# CH32V203RBT6-R1.net
KiCad netlist of a schematic drawn in Altium Designer
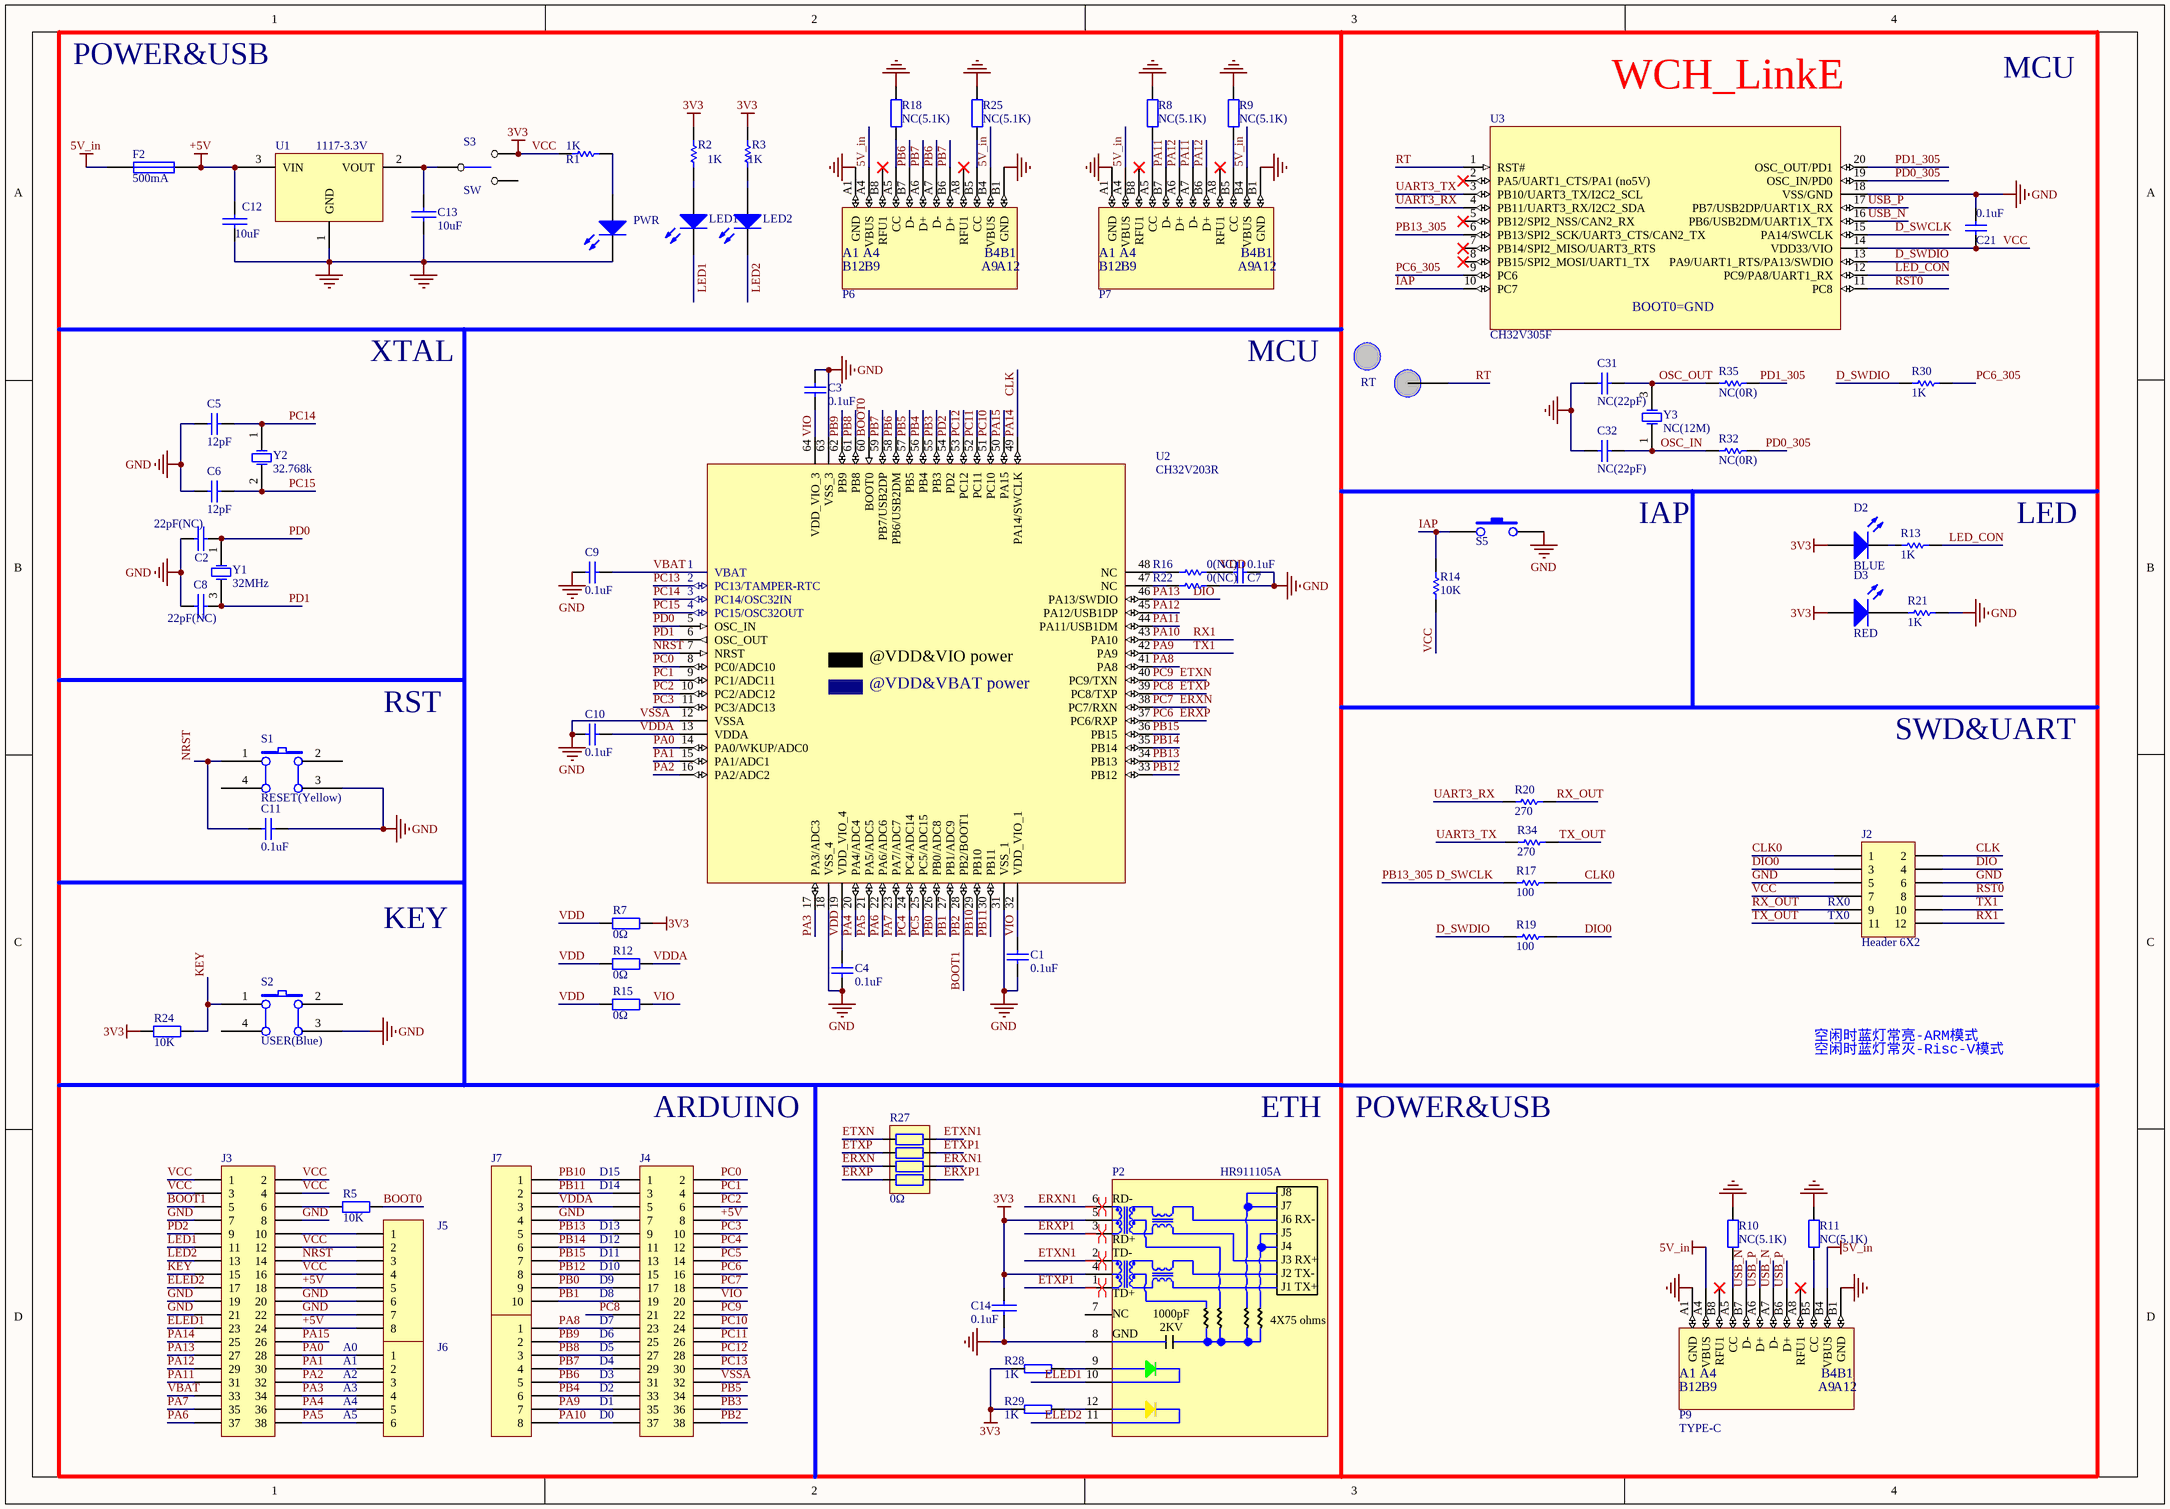
[diagram p0: CH32V203RBT6-R1.SchDoc]

(export (version "E")
  (design (tool "Eeschema 10.0.6"))
  (components
    (comp (ref "C1")
      (value "0.1uF")
      (footprint "0603_C")
      (description "Capacitor")
      (libsource (lib "Miscellaneous Devices") (part "Cap"))
    )
    (comp (ref "C2")
      (value "22pF(NC)")
      (footprint "0603_C")
      (description "Capacitor")
      (libsource (lib "*") (part "CAP"))
    )
    (comp (ref "C3")
      (value "0.1uF")
      (footprint "0603_C")
      (description "Capacitor")
      (libsource (lib "Miscellaneous Devices") (part "Cap"))
    )
    (comp (ref "C4")
      (value "0.1uF")
      (footprint "0603_C")
      (description "Capacitor")
      (libsource (lib "Miscellaneous Devices") (part "Cap"))
    )
    (comp (ref "C5")
      (value "12pF")
      (footprint "0603_C")
      (description "Capacitor")
      (libsource (lib "Miscellaneous Devices") (part "Cap"))
    )
    (comp (ref "C6")
      (value "12pF")
      (footprint "0603_C")
      (description "Capacitor")
      (libsource (lib "Miscellaneous Devices") (part "Cap"))
    )
    (comp (ref "C7")
      (value "0.1uF")
      (footprint "0603_C")
      (description "Capacitor")
      (libsource (lib "Miscellaneous Devices") (part "Cap"))
    )
    (comp (ref "C8")
      (value "22pF(NC)")
      (footprint "0603_C")
      (description "Capacitor")
      (libsource (lib "*") (part "CAP"))
    )
    (comp (ref "C9")
      (value "0.1uF")
      (footprint "0603_C")
      (description "Capacitor")
      (libsource (lib "Miscellaneous Devices") (part "Cap"))
    )
    (comp (ref "C10")
      (value "0.1uF")
      (footprint "0603_C")
      (description "Capacitor")
      (libsource (lib "Miscellaneous Devices") (part "Cap"))
    )
    (comp (ref "C11")
      (value "0.1uF")
      (footprint "0603_C")
      (description "Capacitor")
      (libsource (lib "Miscellaneous Devices") (part "Cap"))
    )
    (comp (ref "C12")
      (value "10uF")
      (footprint "3216_C")
      (description "Capacitor")
      (libsource (lib "*") (part "CAP"))
    )
    (comp (ref "C13")
      (value "10uF")
      (footprint "3216_C")
      (description "Capacitor")
      (libsource (lib "*") (part "CAP"))
    )
    (comp (ref "C14")
      (value "0.1uF")
      (footprint "0603_C")
      (description "Capacitor")
      (libsource (lib "*") (part "CAP"))
    )
    (comp (ref "C21")
      (value "0.1uF")
      (footprint "0603_C")
      (description "Capacitor")
      (libsource (lib "Miscellaneous Devices") (part "Cap"))
    )
    (comp (ref "C31")
      (value "NC(22pF)")
      (footprint "0603_C")
      (description "Capacitor")
      (fields (field (name "PUBLISHER") "Altium Limited"))
      (libsource (lib "*") (part "Cap"))
    )
    (comp (ref "C32")
      (value "NC(22pF)")
      (footprint "0603_C")
      (description "Capacitor")
      (fields (field (name "PUBLISHER") "Altium Limited"))
      (libsource (lib "*") (part "Cap"))
    )
    (comp (ref "D2")
      (value "BLUE")
      (footprint "0603+")
      (description "Typical RED, GREEN, YELLOW, AMBER GaAs LED")
      (fields (field (name "PUBLISHER") "Altium Limited"))
      (libsource (lib "MYLIB") (part "D0603"))
    )
    (comp (ref "D3")
      (value "RED")
      (footprint "0603+")
      (description "Typical RED, GREEN, YELLOW, AMBER GaAs LED")
      (fields (field (name "PUBLISHER") "Altium Limited"))
      (libsource (lib "MYLIB") (part "D0603"))
    )
    (comp (ref "F2")
      (value "500mA")
      (footprint "0805")
      (description "Fuse")
      (libsource (lib "*") (part "FUSE1"))
    )
    (comp (ref "J2")
      (value "Header 6X2")
      (footprint "IDC12-2.54mm")
      (description "Header, 6-Pin, Dual row")
      (fields (field (name "PUBLISHER") "Altium Limited"))
      (libsource (lib "Miscellaneous Connectors") (part "Header 6X2"))
    )
    (comp (ref "J3")
      (value "Header 19X2")
      (footprint "IDC38-2.54mm")
      (description "Header, 19-Pin, Dual row")
      (fields (field (name "PUBLISHER") "Altium Limited"))
      (libsource (lib "Miscellaneous Connectors") (part "Header 19X2"))
    )
    (comp (ref "J4")
      (value "Header 19X2")
      (footprint "IDC38-2.54mm")
      (description "Header, 19-Pin, Dual row")
      (fields (field (name "PUBLISHER") "Altium Limited"))
      (libsource (lib "Miscellaneous Connectors") (part "Header 19X2"))
    )
    (comp (ref "J5")
      (value "Header 8")
      (footprint "SIP8-2.54mm")
      (description "Header, 8-Pin")
      (fields (field (name "PUBLISHER") "Altium Limited"))
      (libsource (lib "") (part "Header 8_1"))
    )
    (comp (ref "J6")
      (value "Header 6")
      (footprint "SIP6-2.54MM")
      (description "Header, 6-Pin")
      (fields (field (name "PUBLISHER") "Altium Limited"))
      (libsource (lib "Miscellaneous Connectors") (part "Header 6"))
    )
    (comp (ref "J7")
      (value "Header 10")
      (footprint "SIP10-2.54mm")
      (description "Header, 10-Pin")
      (fields (field (name "PUBLISHER") "Altium Limited"))
      (libsource (lib "Miscellaneous Connectors") (part "Header 10"))
    )
    (comp (ref "J8")
      (value "Header 8")
      (footprint "SIP8-2.54mm")
      (description "Header, 8-Pin")
      (fields (field (name "PUBLISHER") "Altium Limited"))
      (libsource (lib "Miscellaneous Connectors") (part "Header 8"))
    )
    (comp (ref "LED1")
      (value "LED1   blue")
      (footprint "0603+")
      (description "Typical INFRARED GaAs LED")
      (fields (field (name "PUBLISHER") "Altium Limited"))
      (libsource (lib "Miscellaneous Devices") (part "LED0"))
    )
    (comp (ref "LED2")
      (value "LED2  blue")
      (footprint "0603+")
      (description "Typical INFRARED GaAs LED")
      (fields (field (name "PUBLISHER") "Altium Limited"))
      (libsource (lib "Miscellaneous Devices") (part "LED0"))
    )
    (comp (ref "P2") (value "HR911105A") (footprint "HR911105A") (libsource (lib "*") (part "HR911105A")))
    (comp (ref "P6")
      (value "TYPE-C")
      (footprint "TYPE-C-Receptacle-2.0")
      (libsource (lib "*") (part "TYPE-C1"))
    )
    (comp (ref "P7")
      (value "TYPE-C")
      (footprint "TYPE-C-Receptacle-2.0")
      (libsource (lib "*") (part "TYPE-C1"))
    )
    (comp (ref "P9")
      (value "TYPE-C")
      (footprint "TYPE-C-Receptacle-2.0")
      (libsource (lib "*") (part "TYPE-C1"))
    )
    (comp (ref "PWR")
      (value "POWER  red")
      (footprint "0603+")
      (description "Typical INFRARED GaAs LED")
      (fields (field (name "PUBLISHER") "Altium Limited"))
      (libsource (lib "Miscellaneous Devices") (part "LED0"))
    )
    (comp (ref "R1")
      (value "1K")
      (footprint "0603")
      (description "Semiconductor Resistor")
      (libsource (lib "Miscellaneous Devices") (part "Res Semi"))
    )
    (comp (ref "R2")
      (value "1K")
      (footprint "0603")
      (description "Semiconductor Resistor")
      (libsource (lib "Miscellaneous Devices") (part "Res Semi"))
    )
    (comp (ref "R3")
      (value "1K")
      (footprint "0603")
      (description "Semiconductor Resistor")
      (libsource (lib "Miscellaneous Devices") (part "Res Semi"))
    )
    (comp (ref "R5")
      (value "10K")
      (footprint "0603")
      (description "Resistor")
      (libsource (lib "") (part "Res2_3"))
    )
    (comp (ref "R7")
      (value "0Ω")
      (footprint "0603")
      (description "Resistor")
      (libsource (lib "Miscellaneous Devices") (part "Res2"))
    )
    (comp (ref "R8")
      (value "NC(5.1K)")
      (footprint "0603")
      (description "Resistor")
      (libsource (lib "") (part "Res2_1"))
    )
    (comp (ref "R9")
      (value "NC(5.1K)")
      (footprint "0603")
      (description "Resistor")
      (libsource (lib "") (part "Res2_1"))
    )
    (comp (ref "R10")
      (value "NC(5.1K)")
      (footprint "0603")
      (description "Resistor")
      (libsource (lib "") (part "Res2_2"))
    )
    (comp (ref "R11")
      (value "NC(5.1K)")
      (footprint "0603")
      (description "Resistor")
      (libsource (lib "") (part "Res2_2"))
    )
    (comp (ref "R12")
      (value "0Ω")
      (footprint "0603")
      (description "Resistor")
      (libsource (lib "Miscellaneous Devices") (part "Res2"))
    )
    (comp (ref "R13")
      (value "1K")
      (footprint "0603")
      (description "Resistor")
      (fields (field (name "PUBLISHER") "Altium Limited"))
      (libsource (lib "MYLIB") (part "0603-1"))
    )
    (comp (ref "R14")
      (value "10K")
      (footprint "0603")
      (description "Resistor")
      (fields (field (name "PUBLISHER") "Altium Limited"))
      (libsource (lib "MYLIB") (part "0603-1"))
    )
    (comp (ref "R15")
      (value "0Ω")
      (footprint "0603")
      (description "Resistor")
      (libsource (lib "Miscellaneous Devices") (part "Res2"))
    )
    (comp (ref "R16")
      (value "0(NC)")
      (footprint "0603")
      (description "Resistor")
      (fields (field (name "PUBLISHER") "Altium Limited"))
      (libsource (lib "MYLIB") (part "0603-1"))
    )
    (comp (ref "R17")
      (value "100")
      (footprint "0603")
      (description "Resistor")
      (fields (field (name "PUBLISHER") "Altium Limited"))
      (libsource (lib "MYLIB") (part "0603-1"))
    )
    (comp (ref "R18")
      (value "NC(5.1K)")
      (footprint "0603")
      (description "Resistor")
      (libsource (lib "") (part "Res2_1"))
    )
    (comp (ref "R19")
      (value "100")
      (footprint "0603")
      (description "Resistor")
      (fields (field (name "PUBLISHER") "Altium Limited"))
      (libsource (lib "MYLIB") (part "0603-1"))
    )
    (comp (ref "R20")
      (value "270")
      (footprint "0603")
      (description "Resistor")
      (fields (field (name "PUBLISHER") "Altium Limited"))
      (libsource (lib "MYLIB") (part "0603-1"))
    )
    (comp (ref "R21")
      (value "1K")
      (footprint "0603")
      (description "Resistor")
      (fields (field (name "PUBLISHER") "Altium Limited"))
      (libsource (lib "MYLIB") (part "0603-1"))
    )
    (comp (ref "R22")
      (value "0(NC)")
      (footprint "0603")
      (description "Resistor")
      (fields (field (name "PUBLISHER") "Altium Limited"))
      (libsource (lib "MYLIB") (part "0603-1"))
    )
    (comp (ref "R24")
      (value "10K")
      (footprint "0603")
      (description "Resistor")
      (libsource (lib "Miscellaneous Devices") (part "Res2"))
    )
    (comp (ref "R25")
      (value "NC(5.1K)")
      (footprint "0603")
      (description "Resistor")
      (libsource (lib "") (part "Res2_1"))
    )
    (comp (ref "R27")
      (value "0Ω")
      (footprint "8P4R-0603")
      (description "贴片网络排阻")
      (fields (field (name "版权归属") "源创客"))
      (libsource (lib "wch_sch_others") (part "R-8P4R"))
    )
    (comp (ref "R28") (value "1K") (footprint "0603") (libsource (lib "wch_sch_others") (part "RES")))
    (comp (ref "R29") (value "1K") (footprint "0603") (libsource (lib "wch_sch_others") (part "RES")))
    (comp (ref "R30")
      (value "1K")
      (footprint "0603")
      (description "Resistor")
      (fields (field (name "PUBLISHER") "Altium Limited"))
      (libsource (lib "MYLIB") (part "0603-1"))
    )
    (comp (ref "R32")
      (value "NC(0R)")
      (footprint "0603")
      (description "Resistor")
      (fields (field (name "PUBLISHER") "Altium Limited"))
      (libsource (lib "MYLIB") (part "0603-1"))
    )
    (comp (ref "R34")
      (value "270")
      (footprint "0603")
      (description "Resistor")
      (fields (field (name "PUBLISHER") "Altium Limited"))
      (libsource (lib "MYLIB") (part "0603-1"))
    )
    (comp (ref "R35")
      (value "NC(0R)")
      (footprint "0603")
      (description "Resistor")
      (fields (field (name "PUBLISHER") "Altium Limited"))
      (libsource (lib "MYLIB") (part "0603-1"))
    )
    (comp (ref "RT")
      (value "Testpoint")
      (footprint "TESTPOINT1")
      (description "测试点")
      (libsource (lib "wch_sch_others") (part "Testpoint"))
    )
    (comp (ref "S1")
      (value "RESET(Yellow)")
      (footprint "KEYX")
      (description "SE PUSHBUTTON")
      (libsource (lib "Documents") (part "SW PUSHBUTTON"))
    )
    (comp (ref "S2")
      (value "USER(Blue)")
      (footprint "KEYX")
      (description "SE PUSHBUTTON")
      (libsource (lib "Documents") (part "SW PUSHBUTTON"))
    )
    (comp (ref "S3") (value "SW") (footprint "SW1") (libsource (lib "MYSCH") (part "SW")))
    (comp (ref "S5") (value "KEY") (footprint "贴片按键") (libsource (lib "*") (part "KEY")))
    (comp (ref "U1")
      (value "1117-3.3V")
      (footprint "SOT-223")
      (libsource (lib "wch_sch_others") (part "1117-3.3V"))
    )
    (comp (ref "U2")
      (value "CH32V203R")
      (footprint "LQFP64M_10x10")
      (description "RISC-V HD-MCU, 10M Ethernet, 2*USB, CAN")
      (libsource (lib "CHXXX") (part "CH32V203R"))
    )
    (comp (ref "U3")
      (value "CH32V305F")
      (footprint "TSSOP20")
      (description "RISC-V FPU HD-MCU, 144MHz, USB_480M, CAN, UART*2, SPI")
      (libsource (lib "CHXXX") (part "CH32V305F"))
    )
    (comp (ref "Y1")
      (value "32MHz")
      (footprint "XT3225")
      (description "Crystal Oscillator")
      (fields (field (name "PUBLISHER") "Altium Limited"))
      (libsource (lib "*") (part "XTAL"))
    )
    (comp (ref "Y2")
      (value "32.768k")
      (footprint "FC-135")
      (description "Crystal Oscillator")
      (fields (field (name "PUBLISHER") "Altium Limited"))
      (libsource (lib "Miscellaneous Devices") (part "XTAL"))
    )
    (comp (ref "Y3")
      (value "NC(12M)")
      (footprint "XT3225")
      (description "Crystal Oscillator")
      (libsource (lib "*") (part "XTAL"))
    )
  )
  (nets
    (net (code "1") (name "+5V") (class "Default")
      (node (ref "C12") (pin "1") (pinfunction "1_1") (pintype "passive"))
      (node (ref "F2") (pin "2") (pinfunction "2_2") (pintype "passive"))
      (node (ref "J3") (pin "18") (pinfunction "18_18") (pintype "passive"))
      (node (ref "J3") (pin "24") (pinfunction "24_24") (pintype "passive"))
      (node (ref "J4") (pin "8") (pinfunction "8_8") (pintype "passive"))
      (node (ref "J5") (pin "5") (pinfunction "5_5") (pintype "passive"))
      (node (ref "J5") (pin "8") (pinfunction "8_8") (pintype "passive"))
      (node (ref "U1") (pin "3") (pinfunction "VIN_3") (pintype "passive"))
    )
    (net (code "2") (name "/BOOT0") (class "Default")
      (node (ref "R5") (pin "2") (pinfunction "2_2") (pintype "passive"))
      (node (ref "U2") (pin "60") (pinfunction "BOOT0_60") (pintype "input"))
    )
    (net (code "3") (name "/BOOT1") (class "Default")
      (node (ref "J3") (pin "5") (pinfunction "5_5") (pintype "passive"))
      (node (ref "J4") (pin "38") (pinfunction "38_38") (pintype "passive"))
      (node (ref "U2") (pin "28") (pinfunction "PB2/BOOT1_28") (pintype "bidirectional"))
    )
    (net (code "4") (name "/CLK") (class "Default")
      (node (ref "J2") (pin "2") (pinfunction "2_2") (pintype "passive"))
      (node (ref "J3") (pin "25") (pinfunction "25_25") (pintype "passive"))
      (node (ref "U2") (pin "49") (pinfunction "PA14/SWCLK_49") (pintype "bidirectional"))
    )
    (net (code "5") (name "/CLK0") (class "Default")
      (node (ref "J2") (pin "1") (pinfunction "1_1") (pintype "passive"))
      (node (ref "R17") (pin "1") (pinfunction "1_1") (pintype "passive"))
    )
    (net (code "6") (name "/DIO") (class "Default")
      (node (ref "J2") (pin "4") (pinfunction "4_4") (pintype "passive"))
      (node (ref "J3") (pin "27") (pinfunction "27_27") (pintype "passive"))
      (node (ref "U2") (pin "46") (pinfunction "PA13/SWDIO_46") (pintype "bidirectional"))
    )
    (net (code "7") (name "/DIO0") (class "Default")
      (node (ref "J2") (pin "3") (pinfunction "3_3") (pintype "passive"))
      (node (ref "R19") (pin "1") (pinfunction "1_1") (pintype "passive"))
    )
    (net (code "8") (name "/D_SWCLK") (class "Default")
      (node (ref "R17") (pin "2") (pinfunction "2_2") (pintype "passive"))
      (node (ref "U3") (pin "15") (pinfunction "PA14/SWCLK_15") (pintype "bidirectional"))
      (node (ref "U3") (pin "6") (pinfunction "PB13/SPI2_SCK/UART3_CTS/CAN2_TX_6") (pintype "bidirectional"))
    )
    (net (code "9") (name "/D_SWDIO") (class "Default")
      (node (ref "R19") (pin "2") (pinfunction "2_2") (pintype "passive"))
      (node (ref "R30") (pin "1") (pinfunction "1_1") (pintype "passive"))
      (node (ref "U3") (pin "13") (pinfunction "PA9/UART1_RTS/PA13/SWDIO_13") (pintype "bidirectional"))
    )
    (net (code "10") (name "/ELED1") (class "Default")
      (node (ref "J3") (pin "23") (pinfunction "23_23") (pintype "passive"))
      (node (ref "P2") (pin "10") (pintype "passive"))
    )
    (net (code "11") (name "/ELED2") (class "Default")
      (node (ref "J3") (pin "17") (pinfunction "17_17") (pintype "passive"))
      (node (ref "P2") (pin "11") (pintype "passive"))
    )
    (net (code "12") (name "/ERXN") (class "Default")
      (node (ref "J4") (pin "18") (pinfunction "18_18") (pintype "passive"))
      (node (ref "R27") (pin "3") (pinfunction "3_3") (pintype "passive"))
      (node (ref "U2") (pin "38") (pinfunction "PC7/RXN_38") (pintype "bidirectional"))
    )
    (net (code "13") (name "/ERXN1") (class "Default")
      (node (ref "P2") (pin "6") (pintype "passive"))
      (node (ref "R27") (pin "6") (pinfunction "6_6") (pintype "passive"))
    )
    (net (code "14") (name "/ERXP") (class "Default")
      (node (ref "J4") (pin "16") (pinfunction "16_16") (pintype "passive"))
      (node (ref "R27") (pin "4") (pinfunction "4_4") (pintype "passive"))
      (node (ref "U2") (pin "37") (pinfunction "PC6/RXP_37") (pintype "bidirectional"))
    )
    (net (code "15") (name "/ERXP1") (class "Default")
      (node (ref "P2") (pin "3") (pintype "passive"))
      (node (ref "R27") (pin "5") (pinfunction "5_5") (pintype "passive"))
    )
    (net (code "16") (name "/ETXN") (class "Default")
      (node (ref "J4") (pin "22") (pinfunction "22_22") (pintype "passive"))
      (node (ref "R27") (pin "1") (pinfunction "1_1") (pintype "passive"))
      (node (ref "U2") (pin "40") (pinfunction "PC9/TXN_40") (pintype "bidirectional"))
    )
    (net (code "17") (name "/ETXN1") (class "Default")
      (node (ref "P2") (pin "2") (pintype "passive"))
      (node (ref "R27") (pin "8") (pinfunction "8_8") (pintype "passive"))
    )
    (net (code "18") (name "/ETXP") (class "Default")
      (node (ref "J4") (pin "21") (pinfunction "21_21") (pintype "passive"))
      (node (ref "R27") (pin "2") (pinfunction "2_2") (pintype "passive"))
      (node (ref "U2") (pin "39") (pinfunction "PC8/TXP_39") (pintype "bidirectional"))
    )
    (net (code "19") (name "/ETXP1") (class "Default")
      (node (ref "P2") (pin "1") (pintype "passive"))
      (node (ref "R27") (pin "7") (pinfunction "7_7") (pintype "passive"))
    )
    (net (code "20") (name "/IAP") (class "Default")
      (node (ref "R14") (pin "1") (pinfunction "1_1") (pintype "passive"))
      (node (ref "S5") (pin "1") (pinfunction "1_1") (pintype "passive"))
      (node (ref "U3") (pin "10") (pinfunction "PC7_10") (pintype "bidirectional"))
    )
    (net (code "21") (name "/KEY") (class "Default")
      (node (ref "J3") (pin "15") (pinfunction "15_15") (pintype "passive"))
      (node (ref "R24") (pin "1") (pinfunction "1_1") (pintype "passive"))
      (node (ref "S2") (pin "1") (pinfunction "A0_1") (pintype "passive"))
    )
    (net (code "22") (name "/LED1") (class "Default")
      (node (ref "J3") (pin "11") (pinfunction "11_11") (pintype "passive"))
      (node (ref "LED1") (pin "2") (pinfunction "K_2") (pintype "passive"))
    )
    (net (code "23") (name "/LED2") (class "Default")
      (node (ref "J3") (pin "13") (pinfunction "13_13") (pintype "passive"))
      (node (ref "LED2") (pin "2") (pinfunction "K_2") (pintype "passive"))
    )
    (net (code "24") (name "/LED_CON") (class "Default")
      (node (ref "R13") (pin "1") (pinfunction "1_1") (pintype "passive"))
      (node (ref "U3") (pin "12") (pinfunction "PC9/PA8/UART1_RX_12") (pintype "bidirectional"))
    )
    (net (code "25") (name "/NRST") (class "Default")
      (node (ref "C11") (pin "2") (pinfunction "2_2") (pintype "passive"))
      (node (ref "J3") (pin "14") (pinfunction "14_14") (pintype "passive"))
      (node (ref "J5") (pin "3") (pinfunction "3_3") (pintype "passive"))
      (node (ref "S1") (pin "1") (pinfunction "A0_1") (pintype "passive"))
      (node (ref "U2") (pin "7") (pinfunction "NRST_7") (pintype "input"))
    )
    (net (code "26") (name "/OSC_IN") (class "Default")
      (node (ref "C32") (pin "2") (pinfunction "2_2") (pintype "passive"))
      (node (ref "R32") (pin "2") (pinfunction "2_2") (pintype "passive"))
      (node (ref "Y3") (pin "1") (pinfunction "OSC1_1") (pintype "passive"))
    )
    (net (code "27") (name "/OSC_OUT") (class "Default")
      (node (ref "C31") (pin "2") (pinfunction "2_2") (pintype "passive"))
      (node (ref "R35") (pin "2") (pinfunction "2_2") (pintype "passive"))
      (node (ref "Y3") (pin "3") (pinfunction "OSC2_3") (pintype "passive"))
    )
    (net (code "28") (name "/PA0") (class "Default")
      (node (ref "J3") (pin "28") (pinfunction "28_28") (pintype "passive"))
      (node (ref "J6") (pin "1") (pinfunction "1_1") (pintype "passive"))
      (node (ref "U2") (pin "14") (pinfunction "PA0/WKUP/ADC0_14") (pintype "bidirectional"))
    )
    (net (code "29") (name "/PA1") (class "Default")
      (node (ref "J3") (pin "30") (pinfunction "30_30") (pintype "passive"))
      (node (ref "J6") (pin "2") (pinfunction "2_2") (pintype "passive"))
      (node (ref "U2") (pin "15") (pinfunction "PA1/ADC1_15") (pintype "bidirectional"))
    )
    (net (code "30") (name "/PA2") (class "Default")
      (node (ref "J3") (pin "32") (pinfunction "32_32") (pintype "passive"))
      (node (ref "J6") (pin "3") (pinfunction "3_3") (pintype "passive"))
      (node (ref "U2") (pin "16") (pinfunction "PA2/ADC2_16") (pintype "bidirectional"))
    )
    (net (code "31") (name "/PA3") (class "Default")
      (node (ref "J3") (pin "34") (pinfunction "34_34") (pintype "passive"))
      (node (ref "J6") (pin "4") (pinfunction "4_4") (pintype "passive"))
      (node (ref "U2") (pin "17") (pinfunction "PA3/ADC3_17") (pintype "bidirectional"))
    )
    (net (code "32") (name "/PA4") (class "Default")
      (node (ref "J3") (pin "36") (pinfunction "36_36") (pintype "passive"))
      (node (ref "J6") (pin "5") (pinfunction "5_5") (pintype "passive"))
      (node (ref "U2") (pin "20") (pinfunction "PA4/ADC4_20") (pintype "bidirectional"))
    )
    (net (code "33") (name "/PA5") (class "Default")
      (node (ref "J3") (pin "38") (pinfunction "38_38") (pintype "passive"))
      (node (ref "J6") (pin "6") (pinfunction "6_6") (pintype "passive"))
      (node (ref "U2") (pin "21") (pinfunction "PA5/ADC5_21") (pintype "bidirectional"))
    )
    (net (code "34") (name "/PA6") (class "Default")
      (node (ref "J3") (pin "37") (pinfunction "37_37") (pintype "passive"))
      (node (ref "U2") (pin "22") (pinfunction "PA6/ADC6_22") (pintype "bidirectional"))
    )
    (net (code "35") (name "/PA7") (class "Default")
      (node (ref "J3") (pin "35") (pinfunction "35_35") (pintype "passive"))
      (node (ref "U2") (pin "23") (pinfunction "PA7/ADC7_23") (pintype "bidirectional"))
    )
    (net (code "36") (name "/PA8") (class "Default")
      (node (ref "J4") (pin "23") (pinfunction "23_23") (pintype "passive"))
      (node (ref "J8") (pin "1") (pinfunction "1_1") (pintype "passive"))
      (node (ref "U2") (pin "41") (pinfunction "PA8_41") (pintype "bidirectional"))
    )
    (net (code "37") (name "/PA9") (class "Default")
      (node (ref "J2") (pin "10") (pinfunction "10_10") (pintype "passive"))
      (node (ref "J4") (pin "35") (pinfunction "35_35") (pintype "passive"))
      (node (ref "J8") (pin "7") (pinfunction "7_7") (pintype "passive"))
      (node (ref "U2") (pin "42") (pinfunction "PA9_42") (pintype "bidirectional"))
    )
    (net (code "38") (name "/PA10") (class "Default")
      (node (ref "J2") (pin "12") (pinfunction "12_12") (pintype "passive"))
      (node (ref "J4") (pin "37") (pinfunction "37_37") (pintype "passive"))
      (node (ref "J8") (pin "8") (pinfunction "8_8") (pintype "passive"))
      (node (ref "U2") (pin "43") (pinfunction "PA10_43") (pintype "bidirectional"))
    )
    (net (code "39") (name "/PA11") (class "Default")
      (node (ref "J3") (pin "31") (pinfunction "31_31") (pintype "passive"))
      (node (ref "P7") (pin "A7") (pinfunction "D-_A7") (pintype "bidirectional"))
      (node (ref "P7") (pin "B7") (pinfunction "D-_B7") (pintype "bidirectional"))
      (node (ref "U2") (pin "44") (pinfunction "PA11/USB1DM_44") (pintype "bidirectional"))
    )
    (net (code "40") (name "/PA12") (class "Default")
      (node (ref "J3") (pin "29") (pinfunction "29_29") (pintype "passive"))
      (node (ref "P7") (pin "A6") (pinfunction "D+_A6") (pintype "bidirectional"))
      (node (ref "P7") (pin "B6") (pinfunction "D+_B6") (pintype "bidirectional"))
      (node (ref "U2") (pin "45") (pinfunction "PA12/USB1DP_45") (pintype "bidirectional"))
    )
    (net (code "41") (name "/PA15") (class "Default")
      (node (ref "J3") (pin "26") (pinfunction "26_26") (pintype "passive"))
      (node (ref "U2") (pin "50") (pinfunction "PA15_50") (pintype "bidirectional"))
    )
    (net (code "42") (name "/PB0") (class "Default")
      (node (ref "J4") (pin "17") (pinfunction "17_17") (pintype "passive"))
      (node (ref "J7") (pin "9") (pinfunction "9_9") (pintype "passive"))
      (node (ref "U2") (pin "26") (pinfunction "PB0/ADC8_26") (pintype "bidirectional"))
    )
    (net (code "43") (name "/PB1") (class "Default")
      (node (ref "J4") (pin "19") (pinfunction "19_19") (pintype "passive"))
      (node (ref "J7") (pin "10") (pinfunction "10_10") (pintype "passive"))
      (node (ref "U2") (pin "27") (pinfunction "PB1/ADC9_27") (pintype "bidirectional"))
    )
    (net (code "44") (name "/PB3") (class "Default")
      (node (ref "J4") (pin "36") (pinfunction "36_36") (pintype "passive"))
      (node (ref "U2") (pin "55") (pinfunction "PB3_55") (pintype "bidirectional"))
    )
    (net (code "45") (name "/PB4") (class "Default")
      (node (ref "J4") (pin "33") (pinfunction "33_33") (pintype "passive"))
      (node (ref "J8") (pin "6") (pinfunction "6_6") (pintype "passive"))
      (node (ref "U2") (pin "56") (pinfunction "PB4_56") (pintype "bidirectional"))
    )
    (net (code "46") (name "/PB5") (class "Default")
      (node (ref "J4") (pin "34") (pinfunction "34_34") (pintype "passive"))
      (node (ref "U2") (pin "57") (pinfunction "PB5_57") (pintype "bidirectional"))
    )
    (net (code "47") (name "/PB6") (class "Default")
      (node (ref "J4") (pin "31") (pinfunction "31_31") (pintype "passive"))
      (node (ref "J8") (pin "5") (pinfunction "5_5") (pintype "passive"))
      (node (ref "P6") (pin "A7") (pinfunction "D-_A7") (pintype "bidirectional"))
      (node (ref "P6") (pin "B7") (pinfunction "D-_B7") (pintype "bidirectional"))
      (node (ref "U2") (pin "58") (pinfunction "PB6/USB2DM_58") (pintype "bidirectional"))
    )
    (net (code "48") (name "/PB7") (class "Default")
      (node (ref "J4") (pin "29") (pinfunction "29_29") (pintype "passive"))
      (node (ref "J8") (pin "4") (pinfunction "4_4") (pintype "passive"))
      (node (ref "P6") (pin "A6") (pinfunction "D+_A6") (pintype "bidirectional"))
      (node (ref "P6") (pin "B6") (pinfunction "D+_B6") (pintype "bidirectional"))
      (node (ref "U2") (pin "59") (pinfunction "PB7/USB2DP_59") (pintype "bidirectional"))
    )
    (net (code "49") (name "/PB8") (class "Default")
      (node (ref "J4") (pin "27") (pinfunction "27_27") (pintype "passive"))
      (node (ref "J8") (pin "3") (pinfunction "3_3") (pintype "passive"))
      (node (ref "U2") (pin "61") (pinfunction "PB8_61") (pintype "bidirectional"))
    )
    (net (code "50") (name "/PB9") (class "Default")
      (node (ref "J4") (pin "25") (pinfunction "25_25") (pintype "passive"))
      (node (ref "J8") (pin "2") (pinfunction "2_2") (pintype "passive"))
      (node (ref "U2") (pin "62") (pinfunction "PB9_62") (pintype "bidirectional"))
    )
    (net (code "51") (name "/PB10") (class "Default")
      (node (ref "J4") (pin "1") (pinfunction "1_1") (pintype "passive"))
      (node (ref "J7") (pin "1") (pinfunction "1_1") (pintype "passive"))
      (node (ref "U2") (pin "29") (pinfunction "PB10_29") (pintype "bidirectional"))
    )
    (net (code "52") (name "/PB11") (class "Default")
      (node (ref "J4") (pin "3") (pinfunction "3_3") (pintype "passive"))
      (node (ref "J7") (pin "2") (pinfunction "2_2") (pintype "passive"))
      (node (ref "U2") (pin "30") (pinfunction "PB11_30") (pintype "bidirectional"))
    )
    (net (code "53") (name "/PB12") (class "Default")
      (node (ref "J4") (pin "15") (pinfunction "15_15") (pintype "passive"))
      (node (ref "J7") (pin "8") (pinfunction "8_8") (pintype "passive"))
      (node (ref "U2") (pin "33") (pinfunction "PB12_33") (pintype "bidirectional"))
    )
    (net (code "54") (name "/PB13") (class "Default")
      (node (ref "J4") (pin "9") (pinfunction "9_9") (pintype "passive"))
      (node (ref "J7") (pin "5") (pinfunction "5_5") (pintype "passive"))
      (node (ref "U2") (pin "34") (pinfunction "PB13_34") (pintype "bidirectional"))
    )
    (net (code "55") (name "/PB14") (class "Default")
      (node (ref "J4") (pin "11") (pinfunction "11_11") (pintype "passive"))
      (node (ref "J7") (pin "6") (pinfunction "6_6") (pintype "passive"))
      (node (ref "U2") (pin "35") (pinfunction "PB14_35") (pintype "bidirectional"))
    )
    (net (code "56") (name "/PB15") (class "Default")
      (node (ref "J4") (pin "13") (pinfunction "13_13") (pintype "passive"))
      (node (ref "J7") (pin "7") (pinfunction "7_7") (pintype "passive"))
      (node (ref "U2") (pin "36") (pinfunction "PB15_36") (pintype "bidirectional"))
    )
    (net (code "57") (name "/PC0") (class "Default")
      (node (ref "J4") (pin "2") (pinfunction "2_2") (pintype "passive"))
      (node (ref "U2") (pin "8") (pinfunction "PC0/ADC10_8") (pintype "bidirectional"))
    )
    (net (code "58") (name "/PC1") (class "Default")
      (node (ref "J4") (pin "4") (pinfunction "4_4") (pintype "passive"))
      (node (ref "U2") (pin "9") (pinfunction "PC1/ADC11_9") (pintype "bidirectional"))
    )
    (net (code "59") (name "/PC2") (class "Default")
      (node (ref "J4") (pin "6") (pinfunction "6_6") (pintype "passive"))
      (node (ref "U2") (pin "10") (pinfunction "PC2/ADC12_10") (pintype "bidirectional"))
    )
    (net (code "60") (name "/PC3") (class "Default")
      (node (ref "J4") (pin "10") (pinfunction "10_10") (pintype "passive"))
      (node (ref "U2") (pin "11") (pinfunction "PC3/ADC13_11") (pintype "bidirectional"))
    )
    (net (code "61") (name "/PC4") (class "Default")
      (node (ref "J4") (pin "12") (pinfunction "12_12") (pintype "passive"))
      (node (ref "U2") (pin "24") (pinfunction "PC4/ADC14_24") (pintype "bidirectional"))
    )
    (net (code "62") (name "/PC5") (class "Default")
      (node (ref "J4") (pin "14") (pinfunction "14_14") (pintype "passive"))
      (node (ref "U2") (pin "25") (pinfunction "PC5/ADC15_25") (pintype "bidirectional"))
    )
    (net (code "63") (name "/PC6_305") (class "Default")
      (node (ref "R30") (pin "2") (pinfunction "2_2") (pintype "passive"))
      (node (ref "U3") (pin "9") (pinfunction "PC6_9") (pintype "bidirectional"))
    )
    (net (code "64") (name "/PC10") (class "Default")
      (node (ref "J4") (pin "24") (pinfunction "24_24") (pintype "passive"))
      (node (ref "U2") (pin "51") (pinfunction "PC10_51") (pintype "bidirectional"))
    )
    (net (code "65") (name "/PC11") (class "Default")
      (node (ref "J4") (pin "26") (pinfunction "26_26") (pintype "passive"))
      (node (ref "U2") (pin "52") (pinfunction "PC11_52") (pintype "bidirectional"))
    )
    (net (code "66") (name "/PC12") (class "Default")
      (node (ref "J4") (pin "28") (pinfunction "28_28") (pintype "passive"))
      (node (ref "U2") (pin "53") (pinfunction "PC12_53") (pintype "bidirectional"))
    )
    (net (code "67") (name "/PC13") (class "Default")
      (node (ref "J4") (pin "30") (pinfunction "30_30") (pintype "passive"))
      (node (ref "U2") (pin "2") (pinfunction "PC13/TAMPER-RTC_2") (pintype "bidirectional"))
    )
    (net (code "68") (name "/PC14") (class "Default")
      (node (ref "C5") (pin "1") (pinfunction "1_1") (pintype "passive"))
      (node (ref "U2") (pin "3") (pinfunction "PC14/OSC32IN_3") (pintype "bidirectional"))
      (node (ref "Y2") (pin "1") (pinfunction "OSC1_1") (pintype "passive"))
    )
    (net (code "69") (name "/PC15") (class "Default")
      (node (ref "C6") (pin "1") (pinfunction "1_1") (pintype "passive"))
      (node (ref "U2") (pin "4") (pinfunction "PC15/OSC32OUT_4") (pintype "bidirectional"))
      (node (ref "Y2") (pin "2") (pinfunction "OSC2_2") (pintype "passive"))
    )
    (net (code "70") (name "/PD0") (class "Default")
      (node (ref "C2") (pin "2") (pinfunction "2_2") (pintype "passive"))
      (node (ref "U2") (pin "5") (pinfunction "OSC_IN_5") (pintype "input"))
      (node (ref "Y1") (pin "1") (pinfunction "OSC1_1") (pintype "passive"))
    )
    (net (code "71") (name "/PD0_305") (class "Default")
      (node (ref "R32") (pin "1") (pinfunction "1_1") (pintype "passive"))
      (node (ref "U3") (pin "19") (pinfunction "OSC_IN/PD0_19") (pintype "bidirectional"))
    )
    (net (code "72") (name "/PD1") (class "Default")
      (node (ref "C8") (pin "2") (pinfunction "2_2") (pintype "passive"))
      (node (ref "U2") (pin "6") (pinfunction "OSC_OUT_6") (pintype "output"))
      (node (ref "Y1") (pin "3") (pinfunction "OSC2_3") (pintype "passive"))
    )
    (net (code "73") (name "/PD1_305") (class "Default")
      (node (ref "R35") (pin "1") (pinfunction "1_1") (pintype "passive"))
      (node (ref "U3") (pin "20") (pinfunction "OSC_OUT/PD1_20") (pintype "bidirectional"))
    )
    (net (code "74") (name "/PD2") (class "Default")
      (node (ref "J3") (pin "9") (pinfunction "9_9") (pintype "passive"))
      (node (ref "U2") (pin "54") (pinfunction "PD2_54") (pintype "bidirectional"))
    )
    (net (code "75") (name "/RST0") (class "Default")
      (node (ref "J2") (pin "8") (pinfunction "8_8") (pintype "passive"))
      (node (ref "U3") (pin "11") (pinfunction "PC8_11") (pintype "bidirectional"))
    )
    (net (code "76") (name "/RT") (class "Default")
      (node (ref "RT") (pin "1") (pinfunction "point_1") (pintype "passive"))
      (node (ref "U3") (pin "1") (pinfunction "RST#_1") (pintype "input"))
    )
    (net (code "77") (name "/RX_OUT") (class "Default")
      (node (ref "J2") (pin "9") (pinfunction "9_9") (pintype "passive"))
      (node (ref "R20") (pin "1") (pinfunction "1_1") (pintype "passive"))
    )
    (net (code "78") (name "/TX_OUT") (class "Default")
      (node (ref "J2") (pin "11") (pinfunction "11_11") (pintype "passive"))
      (node (ref "R34") (pin "1") (pinfunction "1_1") (pintype "passive"))
    )
    (net (code "79") (name "/UART3_RX") (class "Default")
      (node (ref "R20") (pin "2") (pinfunction "2_2") (pintype "passive"))
      (node (ref "U3") (pin "4") (pinfunction "PB11/UART3_RX/I2C2_SDA_4") (pintype "bidirectional"))
    )
    (net (code "80") (name "/UART3_TX") (class "Default")
      (node (ref "R34") (pin "2") (pinfunction "2_2") (pintype "passive"))
      (node (ref "U3") (pin "3") (pinfunction "PB10/UART3_TX/I2C2_SCL_3") (pintype "bidirectional"))
    )
    (net (code "81") (name "/USB_N") (class "Default")
      (node (ref "P9") (pin "A7") (pinfunction "D-_A7") (pintype "bidirectional"))
      (node (ref "P9") (pin "B7") (pinfunction "D-_B7") (pintype "bidirectional"))
      (node (ref "U3") (pin "16") (pinfunction "PB6/USB2DM/UART1X_TX_16") (pintype "bidirectional"))
    )
    (net (code "82") (name "/USB_P") (class "Default")
      (node (ref "P9") (pin "A6") (pinfunction "D+_A6") (pintype "bidirectional"))
      (node (ref "P9") (pin "B6") (pinfunction "D+_B6") (pintype "bidirectional"))
      (node (ref "U3") (pin "17") (pinfunction "PB7/USB2DP/UART1X_RX_17") (pintype "bidirectional"))
    )
    (net (code "83") (name "/VBAT") (class "Default")
      (node (ref "C9") (pin "1") (pinfunction "1_1") (pintype "passive"))
      (node (ref "J3") (pin "33") (pinfunction "33_33") (pintype "passive"))
      (node (ref "U2") (pin "1") (pinfunction "VBAT_1") (pintype "power_in"))
    )
    (net (code "84") (name "/VDD") (class "Default")
      (node (ref "C4") (pin "2") (pinfunction "2_2") (pintype "passive"))
      (node (ref "C7") (pin "2") (pinfunction "2_2") (pintype "passive"))
      (node (ref "R12") (pin "2") (pinfunction "2_2") (pintype "passive"))
      (node (ref "R15") (pin "2") (pinfunction "2_2") (pintype "passive"))
      (node (ref "R16") (pin "1") (pinfunction "1_1") (pintype "passive"))
      (node (ref "R7") (pin "2") (pinfunction "2_2") (pintype "passive"))
      (node (ref "U2") (pin "19") (pinfunction "VDD_VIO_4_19") (pintype "power_in"))
    )
    (net (code "85") (name "/VDDA") (class "Default")
      (node (ref "C10") (pin "1") (pinfunction "1_1") (pintype "passive"))
      (node (ref "J4") (pin "5") (pinfunction "5_5") (pintype "passive"))
      (node (ref "J7") (pin "3") (pinfunction "3_3") (pintype "passive"))
      (node (ref "R12") (pin "1") (pinfunction "1_1") (pintype "passive"))
      (node (ref "U2") (pin "13") (pinfunction "VDDA_13") (pintype "power_in"))
    )
    (net (code "86") (name "/VIO") (class "Default")
      (node (ref "C1") (pin "2") (pinfunction "2_2") (pintype "passive"))
      (node (ref "C3") (pin "2") (pinfunction "2_2") (pintype "passive"))
      (node (ref "J4") (pin "20") (pinfunction "20_20") (pintype "passive"))
      (node (ref "R15") (pin "1") (pinfunction "1_1") (pintype "passive"))
      (node (ref "U2") (pin "32") (pinfunction "VDD_VIO_1_32") (pintype "power_in"))
      (node (ref "U2") (pin "64") (pinfunction "VDD_VIO_3_64") (pintype "power_in"))
    )
    (net (code "87") (name "3V3") (class "Default")
      (node (ref "C14") (pin "2") (pinfunction "2_2") (pintype "passive"))
      (node (ref "C21") (pin "1") (pinfunction "1_1") (pintype "passive"))
      (node (ref "D2") (pin "1") (pinfunction "A_1") (pintype "passive"))
      (node (ref "D3") (pin "1") (pinfunction "A_1") (pintype "passive"))
      (node (ref "J2") (pin "7") (pinfunction "7_7") (pintype "passive"))
      (node (ref "J3") (pin "1") (pinfunction "1_1") (pintype "passive"))
      (node (ref "J3") (pin "12") (pinfunction "12_12") (pintype "passive"))
      (node (ref "J3") (pin "16") (pinfunction "16_16") (pintype "passive"))
      (node (ref "J3") (pin "2") (pinfunction "2_2") (pintype "passive"))
      (node (ref "J3") (pin "3") (pinfunction "3_3") (pintype "passive"))
      (node (ref "J3") (pin "4") (pinfunction "4_4") (pintype "passive"))
      (node (ref "J5") (pin "2") (pinfunction "2_2") (pintype "passive"))
      (node (ref "J5") (pin "4") (pinfunction "4_4") (pintype "passive"))
      (node (ref "P2") (pin "4") (pintype "passive"))
      (node (ref "P2") (pin "5") (pintype "passive"))
      (node (ref "R1") (pin "2") (pinfunction "2_2") (pintype "passive"))
      (node (ref "R14") (pin "2") (pinfunction "2_2") (pintype "passive"))
      (node (ref "R2") (pin "1") (pinfunction "1_1") (pintype "passive"))
      (node (ref "R24") (pin "2") (pinfunction "2_2") (pintype "passive"))
      (node (ref "R28") (pin "1") (pintype "passive"))
      (node (ref "R29") (pin "1") (pintype "passive"))
      (node (ref "R3") (pin "1") (pinfunction "1_1") (pintype "passive"))
      (node (ref "R7") (pin "1") (pinfunction "1_1") (pintype "passive"))
      (node (ref "S3") (pin "3") (pinfunction "3_3") (pintype "passive"))
      (node (ref "U3") (pin "14") (pinfunction "VDD33/VIO_14") (pintype "power_in"))
    )
    (net (code "88") (name "5V_in") (class "Default")
      (node (ref "F2") (pin "1") (pinfunction "1_1") (pintype "passive"))
      (node (ref "P6") (pin "A4") (pinfunction "VBUS_A4") (pintype "bidirectional"))
      (node (ref "P6") (pin "B4") (pinfunction "VBUS_B4") (pintype "bidirectional"))
      (node (ref "P7") (pin "A4") (pinfunction "VBUS_A4") (pintype "bidirectional"))
      (node (ref "P7") (pin "B4") (pinfunction "VBUS_B4") (pintype "bidirectional"))
      (node (ref "P9") (pin "A4") (pinfunction "VBUS_A4") (pintype "bidirectional"))
      (node (ref "P9") (pin "B4") (pinfunction "VBUS_B4") (pintype "bidirectional"))
    )
    (net (code "89") (name "GND") (class "Default")
      (node (ref "C1") (pin "1") (pinfunction "1_1") (pintype "passive"))
      (node (ref "C10") (pin "2") (pinfunction "2_2") (pintype "passive"))
      (node (ref "C11") (pin "1") (pinfunction "1_1") (pintype "passive"))
      (node (ref "C12") (pin "2") (pinfunction "2_2") (pintype "passive"))
      (node (ref "C13") (pin "2") (pinfunction "2_2") (pintype "passive"))
      (node (ref "C14") (pin "1") (pinfunction "1_1") (pintype "passive"))
      (node (ref "C2") (pin "1") (pinfunction "1_1") (pintype "passive"))
      (node (ref "C21") (pin "2") (pinfunction "2_2") (pintype "passive"))
      (node (ref "C3") (pin "1") (pinfunction "1_1") (pintype "passive"))
      (node (ref "C31") (pin "1") (pinfunction "1_1") (pintype "passive"))
      (node (ref "C32") (pin "1") (pinfunction "1_1") (pintype "passive"))
      (node (ref "C4") (pin "1") (pinfunction "1_1") (pintype "passive"))
      (node (ref "C5") (pin "2") (pinfunction "2_2") (pintype "passive"))
      (node (ref "C6") (pin "2") (pinfunction "2_2") (pintype "passive"))
      (node (ref "C7") (pin "1") (pinfunction "1_1") (pintype "passive"))
      (node (ref "C8") (pin "1") (pinfunction "1_1") (pintype "passive"))
      (node (ref "C9") (pin "2") (pinfunction "2_2") (pintype "passive"))
      (node (ref "J2") (pin "5") (pinfunction "5_5") (pintype "passive"))
      (node (ref "J2") (pin "6") (pinfunction "6_6") (pintype "passive"))
      (node (ref "J3") (pin "19") (pinfunction "19_19") (pintype "passive"))
      (node (ref "J3") (pin "20") (pinfunction "20_20") (pintype "passive"))
      (node (ref "J3") (pin "21") (pinfunction "21_21") (pintype "passive"))
      (node (ref "J3") (pin "22") (pinfunction "22_22") (pintype "passive"))
      (node (ref "J3") (pin "7") (pinfunction "7_7") (pintype "passive"))
      (node (ref "J3") (pin "8") (pinfunction "8_8") (pintype "passive"))
      (node (ref "J4") (pin "32") (pinfunction "32_32") (pintype "passive"))
      (node (ref "J4") (pin "7") (pinfunction "7_7") (pintype "passive"))
      (node (ref "J5") (pin "6") (pinfunction "6_6") (pintype "passive"))
      (node (ref "J5") (pin "7") (pinfunction "7_7") (pintype "passive"))
      (node (ref "J7") (pin "4") (pinfunction "4_4") (pintype "passive"))
      (node (ref "P2") (pin "8") (pintype "passive"))
      (node (ref "P6") (pin "A1") (pinfunction "GND_A1") (pintype "bidirectional"))
      (node (ref "P6") (pin "B1") (pinfunction "GND_B1") (pintype "bidirectional"))
      (node (ref "P7") (pin "A1") (pinfunction "GND_A1") (pintype "bidirectional"))
      (node (ref "P7") (pin "B1") (pinfunction "GND_B1") (pintype "bidirectional"))
      (node (ref "P9") (pin "A1") (pinfunction "GND_A1") (pintype "bidirectional"))
      (node (ref "P9") (pin "B1") (pinfunction "GND_B1") (pintype "bidirectional"))
      (node (ref "PWR") (pin "2") (pinfunction "K_2") (pintype "passive"))
      (node (ref "R10") (pin "2") (pinfunction "2_2") (pintype "passive"))
      (node (ref "R11") (pin "2") (pinfunction "2_2") (pintype "passive"))
      (node (ref "R18") (pin "1") (pinfunction "1_1") (pintype "passive"))
      (node (ref "R21") (pin "1") (pinfunction "1_1") (pintype "passive"))
      (node (ref "R22") (pin "1") (pinfunction "1_1") (pintype "passive"))
      (node (ref "R25") (pin "1") (pinfunction "1_1") (pintype "passive"))
      (node (ref "R8") (pin "1") (pinfunction "1_1") (pintype "passive"))
      (node (ref "R9") (pin "1") (pinfunction "1_1") (pintype "passive"))
      (node (ref "S1") (pin "3") (pinfunction "B1_3") (pintype "passive"))
      (node (ref "S2") (pin "3") (pinfunction "B1_3") (pintype "passive"))
      (node (ref "S5") (pin "2") (pinfunction "2_2") (pintype "passive"))
      (node (ref "U1") (pin "1") (pinfunction "GND_1") (pintype "passive"))
      (node (ref "U2") (pin "12") (pinfunction "VSSA_12") (pintype "power_in"))
      (node (ref "U2") (pin "18") (pinfunction "VSS_4_18") (pintype "power_in"))
      (node (ref "U2") (pin "31") (pinfunction "VSS_1_31") (pintype "power_in"))
      (node (ref "U2") (pin "63") (pinfunction "VSS_3_63") (pintype "power_in"))
      (node (ref "U3") (pin "18") (pinfunction "VSS/GND_18") (pintype "power_in"))
    )
    (net (code "90") (name "Net-(D2-K)") (class "Default")
      (node (ref "D2") (pin "2") (pinfunction "K_2") (pintype "passive"))
      (node (ref "R13") (pin "2") (pinfunction "2_2") (pintype "passive"))
    )
    (net (code "91") (name "Net-(D3-K)") (class "Default")
      (node (ref "D3") (pin "2") (pinfunction "K_2") (pintype "passive"))
      (node (ref "R21") (pin "2") (pinfunction "2_2") (pintype "passive"))
    )
    (net (code "92") (name "Net-(J3-Pad6)") (class "Default")
      (node (ref "J3") (pin "6") (pinfunction "6_6") (pintype "passive"))
      (node (ref "R5") (pin "1") (pinfunction "1_1") (pintype "passive"))
    )
    (net (code "93") (name "Net-(J3-Pad10)") (class "Default")
      (node (ref "J3") (pin "10") (pinfunction "10_10") (pintype "passive"))
      (node (ref "J5") (pin "1") (pinfunction "1_1") (pintype "passive"))
    )
    (net (code "94") (name "Net-(LED1-A)") (class "Default")
      (node (ref "LED1") (pin "1") (pinfunction "A_1") (pintype "passive"))
      (node (ref "R2") (pin "2") (pinfunction "2_2") (pintype "passive"))
    )
    (net (code "95") (name "Net-(LED2-A)") (class "Default")
      (node (ref "LED2") (pin "1") (pinfunction "A_1") (pintype "passive"))
      (node (ref "R3") (pin "2") (pinfunction "2_2") (pintype "passive"))
    )
    (net (code "96") (name "Net-(P2-Pad9)") (class "Default")
      (node (ref "P2") (pin "9") (pintype "passive"))
      (node (ref "R28") (pin "2") (pintype "passive"))
    )
    (net (code "97") (name "Net-(P2-Pad12)") (class "Default")
      (node (ref "P2") (pin "12") (pintype "passive"))
      (node (ref "R29") (pin "2") (pintype "passive"))
    )
    (net (code "98") (name "Net-(P6-CC-PadA5)") (class "Default")
      (node (ref "P6") (pin "A5") (pinfunction "CC_A5") (pintype "bidirectional"))
      (node (ref "R18") (pin "2") (pinfunction "2_2") (pintype "passive"))
    )
    (net (code "99") (name "Net-(P6-CC-PadB5)") (class "Default")
      (node (ref "P6") (pin "B5") (pinfunction "CC_B5") (pintype "bidirectional"))
      (node (ref "R25") (pin "2") (pinfunction "2_2") (pintype "passive"))
    )
    (net (code "100") (name "Net-(P7-CC-PadA5)") (class "Default")
      (node (ref "P7") (pin "A5") (pinfunction "CC_A5") (pintype "bidirectional"))
      (node (ref "R8") (pin "2") (pinfunction "2_2") (pintype "passive"))
    )
    (net (code "101") (name "Net-(P7-CC-PadB5)") (class "Default")
      (node (ref "P7") (pin "B5") (pinfunction "CC_B5") (pintype "bidirectional"))
      (node (ref "R9") (pin "2") (pinfunction "2_2") (pintype "passive"))
    )
    (net (code "102") (name "Net-(P9-CC-PadA5)") (class "Default")
      (node (ref "P9") (pin "A5") (pinfunction "CC_A5") (pintype "bidirectional"))
      (node (ref "R10") (pin "1") (pinfunction "1_1") (pintype "passive"))
    )
    (net (code "103") (name "Net-(P9-CC-PadB5)") (class "Default")
      (node (ref "P9") (pin "B5") (pinfunction "CC_B5") (pintype "bidirectional"))
      (node (ref "R11") (pin "1") (pinfunction "1_1") (pintype "passive"))
    )
    (net (code "104") (name "Net-(PWR-A)") (class "Default")
      (node (ref "PWR") (pin "1") (pinfunction "A_1") (pintype "passive"))
      (node (ref "R1") (pin "1") (pinfunction "1_1") (pintype "passive"))
    )
    (net (code "105") (name "Net-(R16-Pad2)") (class "Default")
      (node (ref "R16") (pin "2") (pinfunction "2_2") (pintype "passive"))
      (node (ref "U2") (pin "48") (pinfunction "NC_48") (pintype "power_in"))
    )
    (net (code "106") (name "Net-(R22-Pad2)") (class "Default")
      (node (ref "R22") (pin "2") (pinfunction "2_2") (pintype "passive"))
      (node (ref "U2") (pin "47") (pinfunction "NC_47") (pintype "power_in"))
    )
    (net (code "107") (name "Net-(U1-VOUT)") (class "Default")
      (node (ref "C13") (pin "1") (pinfunction "1_1") (pintype "passive"))
      (node (ref "S3") (pin "1") (pinfunction "1_1") (pintype "passive"))
      (node (ref "U1") (pin "2") (pinfunction "VOUT_2") (pintype "passive"))
    )
    (net (code "108") (name "unconnected-(P2-Pad7)") (class "Default")
      (node (ref "P2") (pin "7") (pintype "passive"))
    )
    (net (code "109") (name "unconnected-(P6-RFU1-PadA8)") (class "Default")
      (node (ref "P6") (pin "A8") (pinfunction "RFU1_A8") (pintype "bidirectional+no_connect"))
    )
    (net (code "110") (name "unconnected-(P6-RFU1-PadB8)") (class "Default")
      (node (ref "P6") (pin "B8") (pinfunction "RFU1_B8") (pintype "bidirectional+no_connect"))
    )
    (net (code "111") (name "unconnected-(P7-RFU1-PadA8)") (class "Default")
      (node (ref "P7") (pin "A8") (pinfunction "RFU1_A8") (pintype "bidirectional+no_connect"))
    )
    (net (code "112") (name "unconnected-(P7-RFU1-PadB8)") (class "Default")
      (node (ref "P7") (pin "B8") (pinfunction "RFU1_B8") (pintype "bidirectional+no_connect"))
    )
    (net (code "113") (name "unconnected-(P9-RFU1-PadA8)") (class "Default")
      (node (ref "P9") (pin "A8") (pinfunction "RFU1_A8") (pintype "bidirectional+no_connect"))
    )
    (net (code "114") (name "unconnected-(P9-RFU1-PadB8)") (class "Default")
      (node (ref "P9") (pin "B8") (pinfunction "RFU1_B8") (pintype "bidirectional+no_connect"))
    )
    (net (code "115") (name "unconnected-(S1-A1-Pad4)") (class "Default")
      (node (ref "S1") (pin "4") (pinfunction "A1_4") (pintype "passive"))
    )
    (net (code "116") (name "unconnected-(S1-B0-Pad2)") (class "Default")
      (node (ref "S1") (pin "2") (pinfunction "B0_2") (pintype "passive"))
    )
    (net (code "117") (name "unconnected-(S2-A1-Pad4)") (class "Default")
      (node (ref "S2") (pin "4") (pinfunction "A1_4") (pintype "passive"))
    )
    (net (code "118") (name "unconnected-(S2-B0-Pad2)") (class "Default")
      (node (ref "S2") (pin "2") (pinfunction "B0_2") (pintype "passive"))
    )
    (net (code "119") (name "unconnected-(S3-Pad2)") (class "Default")
      (node (ref "S3") (pin "2") (pinfunction "2_2") (pintype "passive"))
    )
    (net (code "120") (name "unconnected-(U3-PA5{slash}UART1_CTS{slash}PA1_(no5V)-Pad2)") (class "Default")
      (node (ref "U3") (pin "2") (pinfunction "PA5/UART1_CTS/PA1_(no5V)_2") (pintype "bidirectional+no_connect"))
    )
    (net (code "121") (name "unconnected-(U3-PB12{slash}SPI2_NSS{slash}CAN2_RX-Pad5)") (class "Default")
      (node (ref "U3") (pin "5") (pinfunction "PB12/SPI2_NSS/CAN2_RX_5") (pintype "bidirectional+no_connect"))
    )
    (net (code "122") (name "unconnected-(U3-PB14{slash}SPI2_MISO{slash}UART3_RTS-Pad7)") (class "Default")
      (node (ref "U3") (pin "7") (pinfunction "PB14/SPI2_MISO/UART3_RTS_7") (pintype "bidirectional+no_connect"))
    )
    (net (code "123") (name "unconnected-(U3-PB15{slash}SPI2_MOSI{slash}UART1_TX-Pad8)") (class "Default")
      (node (ref "U3") (pin "8") (pinfunction "PB15/SPI2_MOSI/UART1_TX_8") (pintype "bidirectional+no_connect"))
    )
  )
)
